# ACS758CurrentSensor.net
KiCad netlist of a schematic drawn in EAGLE
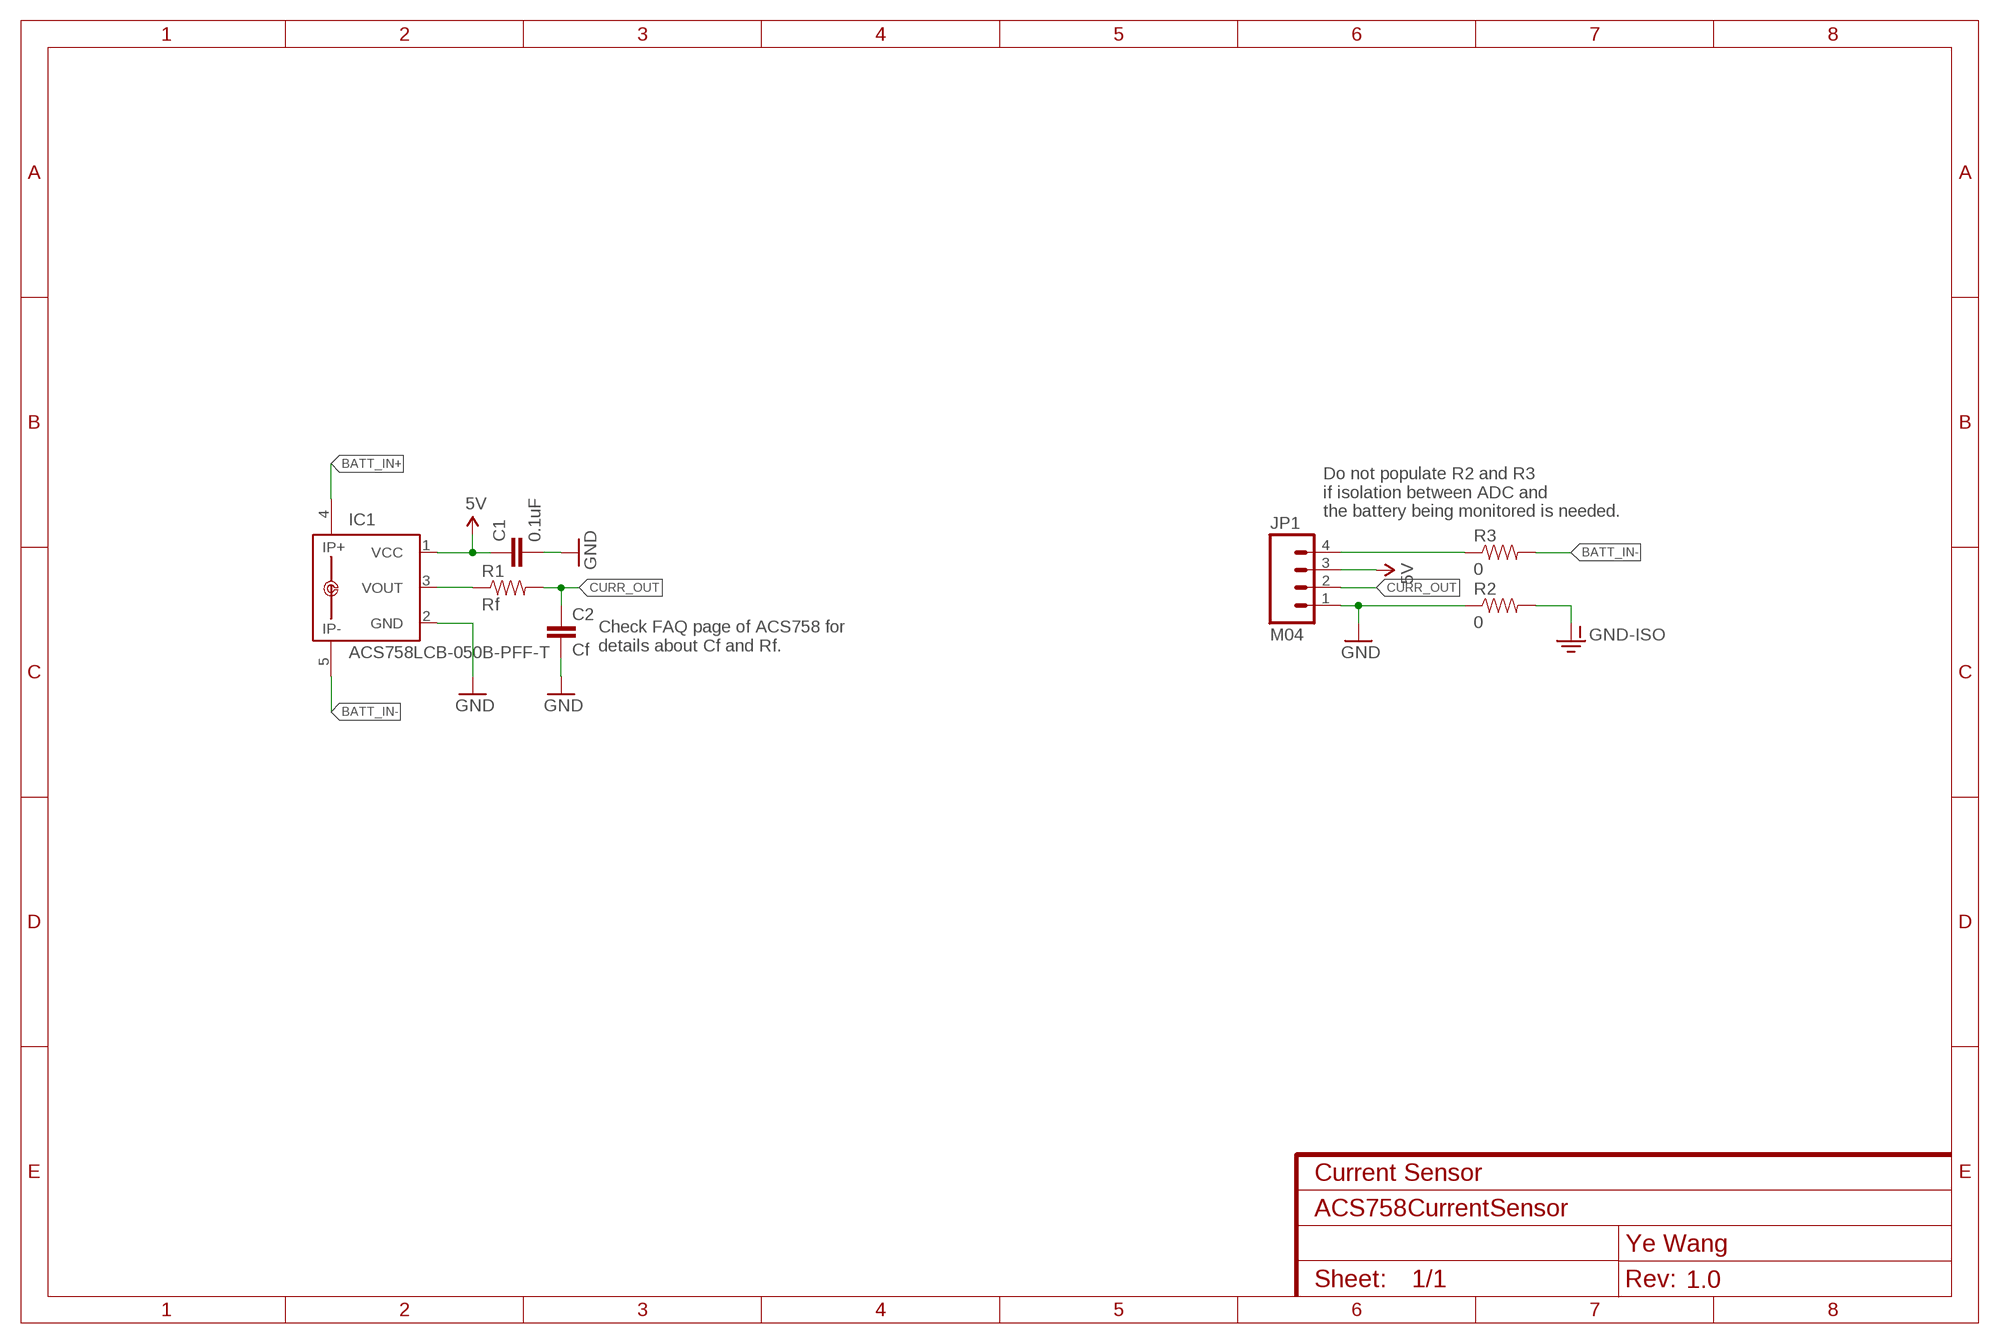
[diagram p0: schematic, sheet 1]

(export (version "E")
  (design (tool "Eeschema 10.0.6"))
  (components
    (comp (ref "C1")
      (value "0.1uF")
      (footprint "eagle-import:0603-CAP")
      (libsource (lib "eagle-import") (part "CAP0603-CAP"))
    )
    (comp (ref "C2")
      (value "Cf")
      (footprint "eagle-import:0603-CAP")
      (libsource (lib "eagle-import") (part "CAP0603-CAP"))
    )
    (comp (ref "IC1")
      (value "ACS758LCB-050B-PFF-T")
      (footprint "eagle-import:CB-PFF")
      (libsource (lib "eagle-import") (part "ACS758LCB-050B-PFF-T"))
    )
    (comp (ref "JP1")
      (value "M04")
      (footprint "eagle-import:1X04")
      (libsource (lib "eagle-import") (part "M04PTH"))
    )
    (comp (ref "R1")
      (value "Rf")
      (footprint "eagle-import:0603")
      (libsource (lib "eagle-import") (part "0OHM-1/10W-5%(0603)"))
    )
    (comp (ref "R2")
      (value "0")
      (footprint "eagle-import:0603")
      (libsource (lib "eagle-import") (part "0OHM-1/10W-5%(0603)"))
    )
    (comp (ref "R3")
      (value "0")
      (footprint "eagle-import:0603")
      (libsource (lib "eagle-import") (part "0OHM-1/10W-5%(0603)"))
    )
  )
  (nets
    (net (code "1") (name "5V") (class "Default")
      (node (ref "C1") (pin "1") (pinfunction "1_1") (pintype "passive"))
      (node (ref "IC1") (pin "1") (pinfunction "VCC_1") (pintype "power_in"))
      (node (ref "JP1") (pin "3") (pinfunction "3_3") (pintype "passive"))
    )
    (net (code "2") (name "BATT_IN+") (class "Default")
      (node (ref "IC1") (pin "4") (pinfunction "IP+_4") (pintype "passive"))
    )
    (net (code "3") (name "BATT_IN-") (class "Default")
      (node (ref "IC1") (pin "5") (pinfunction "IP-_5") (pintype "passive"))
      (node (ref "R3") (pin "2") (pinfunction "2_2") (pintype "passive"))
    )
    (net (code "4") (name "CURR_OUT") (class "Default")
      (node (ref "C2") (pin "1") (pinfunction "1_1") (pintype "passive"))
      (node (ref "JP1") (pin "2") (pinfunction "2_2") (pintype "passive"))
      (node (ref "R1") (pin "2") (pinfunction "2_2") (pintype "passive"))
    )
    (net (code "5") (name "GND") (class "Default")
      (node (ref "C1") (pin "2") (pinfunction "2_2") (pintype "passive"))
      (node (ref "C2") (pin "2") (pinfunction "2_2") (pintype "passive"))
      (node (ref "IC1") (pin "2") (pinfunction "GND_2") (pintype "power_in"))
      (node (ref "JP1") (pin "1") (pinfunction "1_1") (pintype "passive"))
      (node (ref "R2") (pin "1") (pinfunction "1_1") (pintype "passive"))
    )
    (net (code "6") (name "GND-ISO") (class "Default")
      (node (ref "R2") (pin "2") (pinfunction "2_2") (pintype "passive"))
    )
    (net (code "7") (name "Net-(IC1-VOUT)") (class "Default")
      (node (ref "IC1") (pin "3") (pinfunction "VOUT_3") (pintype "output"))
      (node (ref "R1") (pin "1") (pinfunction "1_1") (pintype "passive"))
    )
    (net (code "8") (name "Net-(JP1-Pad4)") (class "Default")
      (node (ref "JP1") (pin "4") (pinfunction "4_4") (pintype "passive"))
      (node (ref "R3") (pin "1") (pinfunction "1_1") (pintype "passive"))
    )
    (net (code "9") (name "unconnected-(IC1-PadIP+1)") (class "Default")
      (node (ref "IC1") (pin "IP+1") (pinfunction "IP+1_IP+1") (pintype "input"))
    )
    (net (code "10") (name "unconnected-(IC1-PadIP-1)") (class "Default")
      (node (ref "IC1") (pin "IP-1") (pinfunction "IP-1_IP-1") (pintype "input"))
    )
  )
)
